# nigme1_Switch.net
KiCad netlist of a schematic drawn in Altium Designer
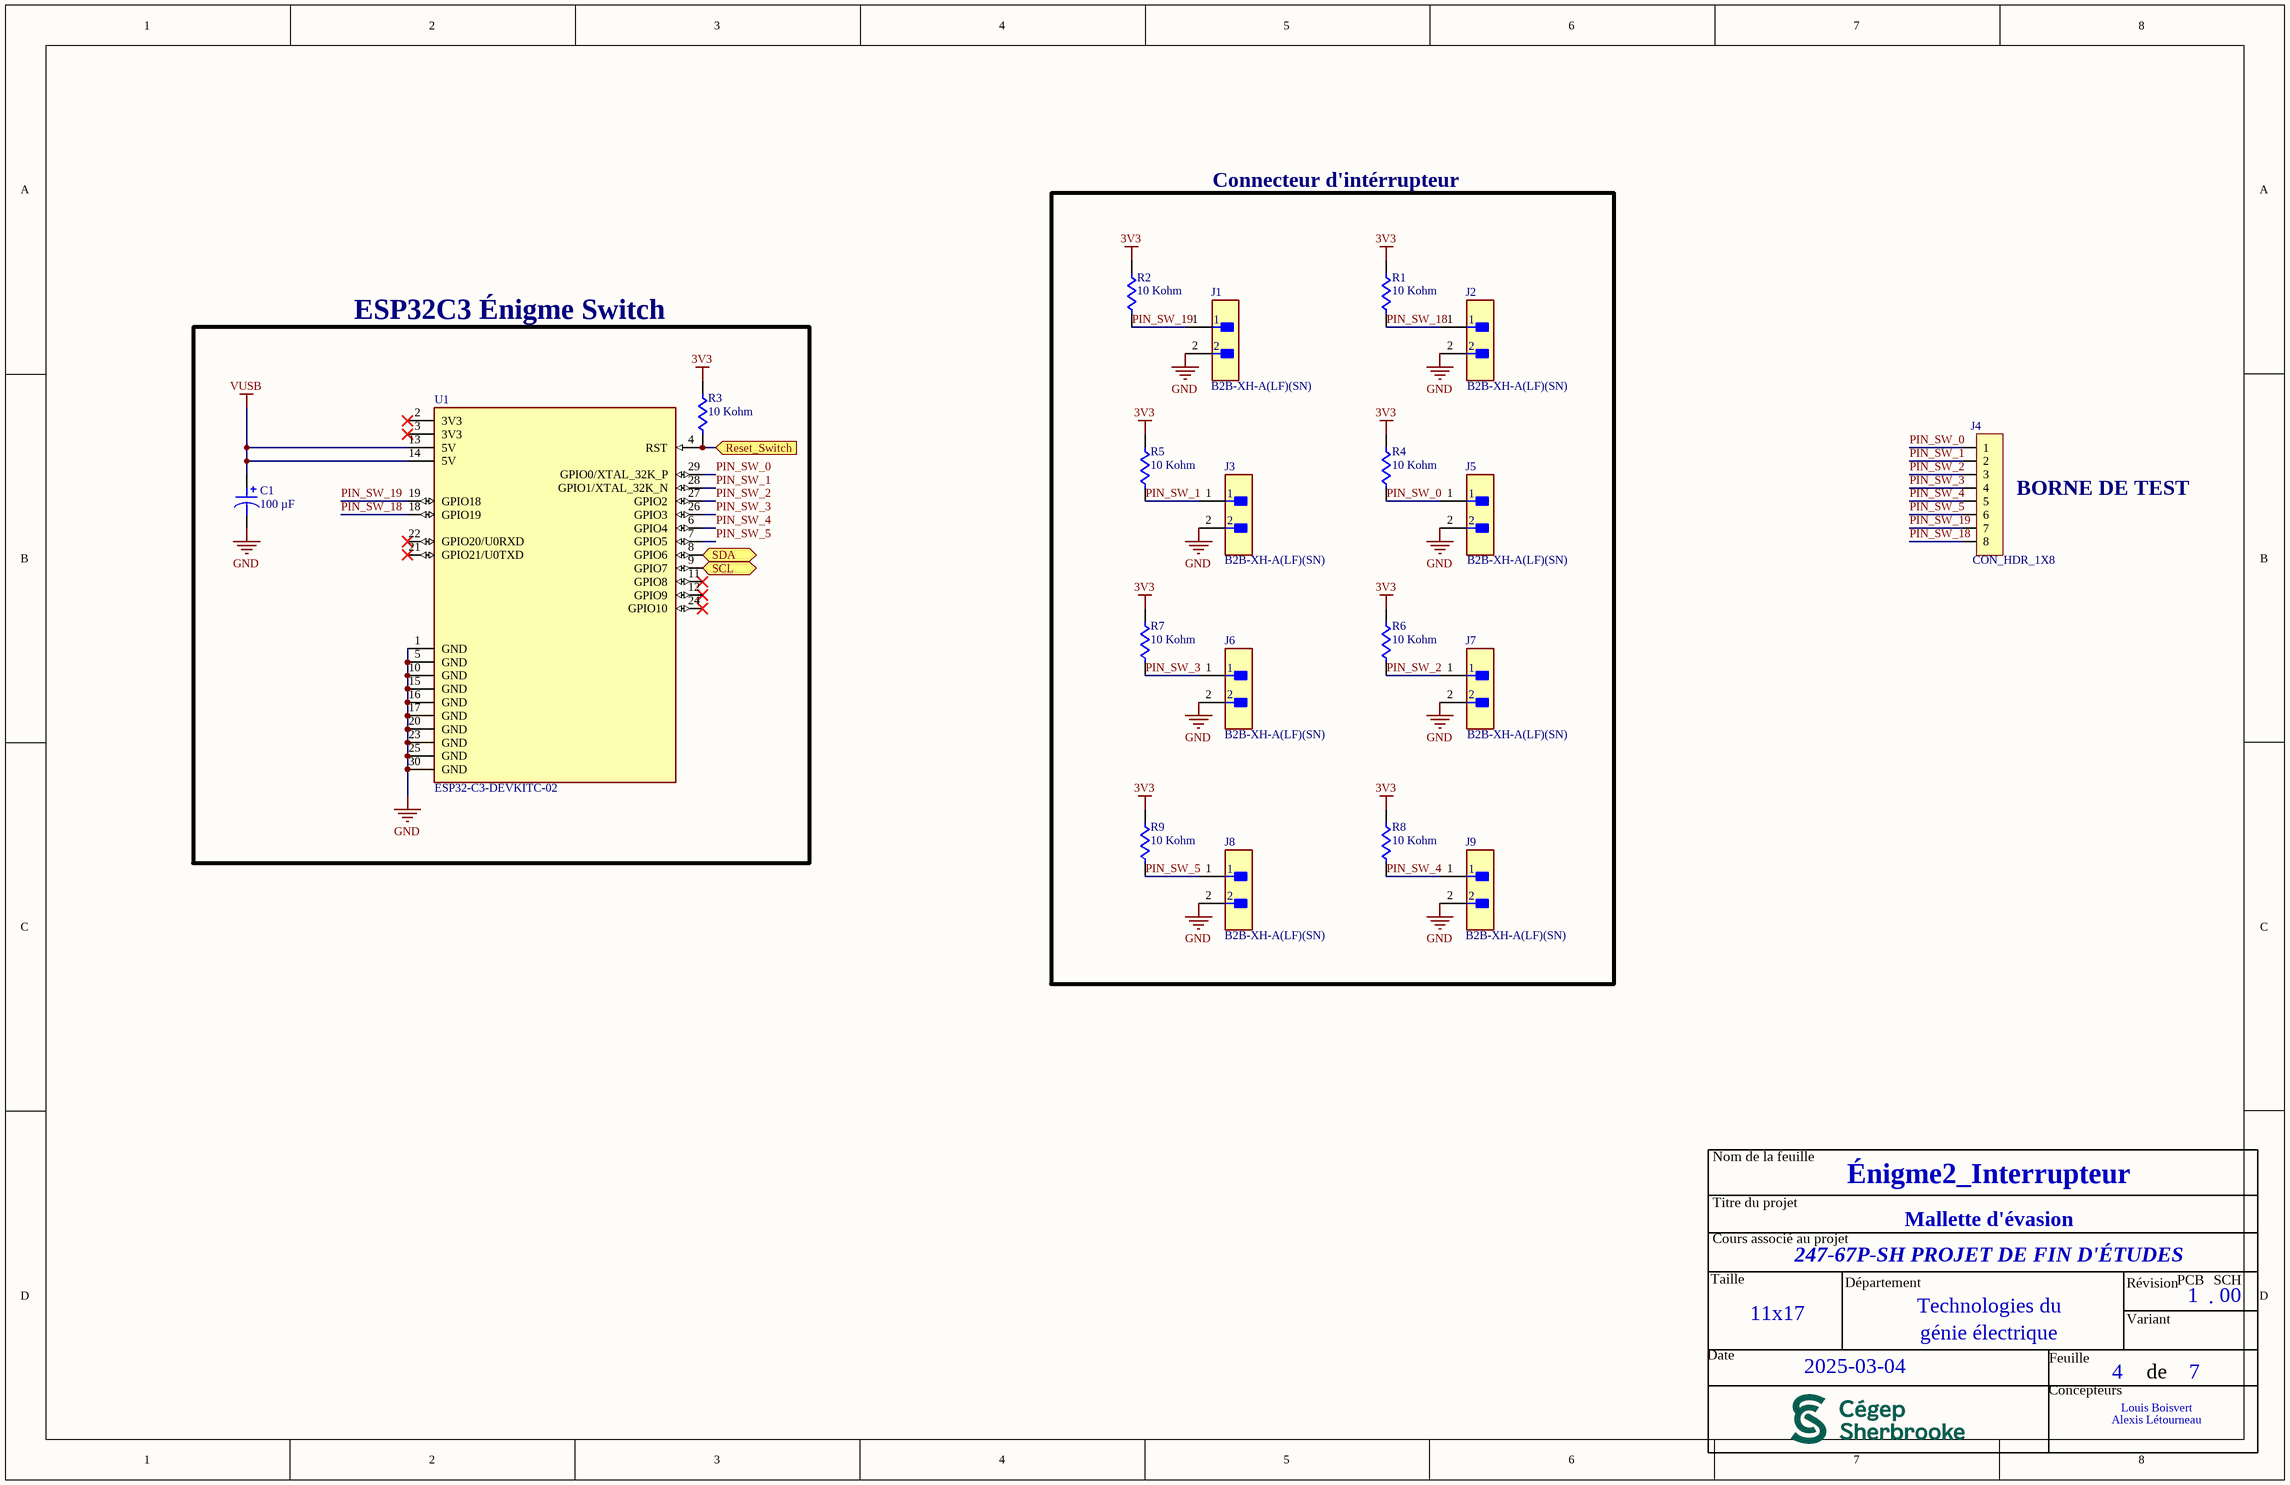
[diagram p0: Énigme1_Switch.SchDoc]

(export (version "E")
  (design (tool "Eeschema 10.0.6"))
  (components
    (comp (ref "C1")
      (value "100 µF")
      (footprint "CAP AL TH D8 L3.5 H12.5")
      (description "CAP ALUM 100UF 20% 50V RADIAL")
      (fields (field (name "PART NUMBER") "860020674015") (field (name "MANUFACTURER") "Würth Elektronik"))
      (libsource (lib "Celestial Altium Library - altium_library") (part "Polarised Capacitor"))
    )
    (comp (ref "J1")
      (value "B2B-XH-A(LF)(SN)")
      (footprint "FP-B2B-XH-A_LF_SN-MFG")
      (description "CONN HEADER VERT 2POS 2.5MM")
      (libsource (lib "Altium Content Vault") (part "3bc925449376181038e59eaffc5286c"))
    )
    (comp (ref "J2")
      (value "B2B-XH-A(LF)(SN)")
      (footprint "FP-B2B-XH-A_LF_SN-MFG")
      (description "CONN HEADER VERT 2POS 2.5MM")
      (libsource (lib "Altium Content Vault") (part "3bc925449376181038e59eaffc5286c"))
    )
    (comp (ref "J3")
      (value "B2B-XH-A(LF)(SN)")
      (footprint "FP-B2B-XH-A_LF_SN-MFG")
      (description "CONN HEADER VERT 2POS 2.5MM")
      (libsource (lib "Altium Content Vault") (part "3bc925449376181038e59eaffc5286c"))
    )
    (comp (ref "J4")
      (value "CON_HDR_1X8")
      (footprint "CON_HDR_1x8")
      (description "CON - Header 1X8 pins, 100Mils - TH-8")
      (fields (field (name "SOURCE") "CEGEP_SHERBROOKE_TGE_LIBRARY.SchLib"))
      (libsource (lib "Cegep de Sherbrooke") (part "CON_HDR_1X8"))
    )
    (comp (ref "J5")
      (value "B2B-XH-A(LF)(SN)")
      (footprint "FP-B2B-XH-A_LF_SN-MFG")
      (description "CONN HEADER VERT 2POS 2.5MM")
      (libsource (lib "Altium Content Vault") (part "3bc925449376181038e59eaffc5286c"))
    )
    (comp (ref "J6")
      (value "B2B-XH-A(LF)(SN)")
      (footprint "FP-B2B-XH-A_LF_SN-MFG")
      (description "CONN HEADER VERT 2POS 2.5MM")
      (libsource (lib "Altium Content Vault") (part "3bc925449376181038e59eaffc5286c"))
    )
    (comp (ref "J7")
      (value "B2B-XH-A(LF)(SN)")
      (footprint "FP-B2B-XH-A_LF_SN-MFG")
      (description "CONN HEADER VERT 2POS 2.5MM")
      (libsource (lib "Altium Content Vault") (part "3bc925449376181038e59eaffc5286c"))
    )
    (comp (ref "J8")
      (value "B2B-XH-A(LF)(SN)")
      (footprint "FP-B2B-XH-A_LF_SN-MFG")
      (description "CONN HEADER VERT 2POS 2.5MM")
      (libsource (lib "Altium Content Vault") (part "3bc925449376181038e59eaffc5286c"))
    )
    (comp (ref "J9")
      (value "B2B-XH-A(LF)(SN)")
      (footprint "FP-B2B-XH-A_LF_SN-MFG")
      (description "CONN HEADER VERT 2POS 2.5MM")
      (libsource (lib "Altium Content Vault") (part "3bc925449376181038e59eaffc5286c"))
    )
    (comp (ref "R1")
      (value "10 Kohm")
      (footprint "Res_Template")
      (description "Custom Semiconductor Resistor")
      (libsource (lib "Schlib1") (part "470 ohm"))
    )
    (comp (ref "R2")
      (value "10 Kohm")
      (footprint "Res_Template")
      (description "Custom Semiconductor Resistor")
      (libsource (lib "Schlib1") (part "470 ohm"))
    )
    (comp (ref "R3")
      (value "10 Kohm")
      (footprint "Res_Template")
      (description "Custom Semiconductor Resistor")
      (libsource (lib "Schlib1") (part "470 ohm"))
    )
    (comp (ref "R4")
      (value "10 Kohm")
      (footprint "Res_Template")
      (description "Custom Semiconductor Resistor")
      (libsource (lib "Schlib1") (part "470 ohm"))
    )
    (comp (ref "R5")
      (value "10 Kohm")
      (footprint "Res_Template")
      (description "Custom Semiconductor Resistor")
      (libsource (lib "Schlib1") (part "470 ohm"))
    )
    (comp (ref "R6")
      (value "10 Kohm")
      (footprint "Res_Template")
      (description "Custom Semiconductor Resistor")
      (libsource (lib "Schlib1") (part "470 ohm"))
    )
    (comp (ref "R7")
      (value "10 Kohm")
      (footprint "Res_Template")
      (description "Custom Semiconductor Resistor")
      (libsource (lib "Schlib1") (part "470 ohm"))
    )
    (comp (ref "R8")
      (value "10 Kohm")
      (footprint "Res_Template")
      (description "Custom Semiconductor Resistor")
      (libsource (lib "Schlib1") (part "470 ohm"))
    )
    (comp (ref "R9")
      (value "10 Kohm")
      (footprint "Res_Template")
      (description "Custom Semiconductor Resistor")
      (libsource (lib "Schlib1") (part "470 ohm"))
    )
    (comp (ref "U1")
      (value "ESP32-C3-DEVKITC-02")
      (footprint "XCVR_ESP32-C3-DEVKITC-02")
      (fields (field (name "MP") "ESP32-C3-DevKitC-02") (field (name "MF") "Espressif Systems"))
      (libsource (lib "ESP32-C3-DEVKITC-02") (part "ESP32-C3-DEVKITC-02"))
    )
  )
  (nets
    (net (code "1") (name "/PIN_SW_0") (class "Default")
      (node (ref "J4") (pin "1") (pinfunction "1_1") (pintype "passive"))
      (node (ref "J5") (pin "1") (pinfunction "1_1") (pintype "passive"))
      (node (ref "R4") (pin "1") (pinfunction "1_1") (pintype "passive"))
      (node (ref "U1") (pin "29") (pinfunction "GPIO0/XTAL_32K_P_29") (pintype "bidirectional"))
    )
    (net (code "2") (name "/PIN_SW_1") (class "Default")
      (node (ref "J3") (pin "1") (pinfunction "1_1") (pintype "passive"))
      (node (ref "J4") (pin "2") (pinfunction "2_2") (pintype "passive"))
      (node (ref "R5") (pin "1") (pinfunction "1_1") (pintype "passive"))
      (node (ref "U1") (pin "28") (pinfunction "GPIO1/XTAL_32K_N_28") (pintype "bidirectional"))
    )
    (net (code "3") (name "/PIN_SW_2") (class "Default")
      (node (ref "J4") (pin "3") (pinfunction "3_3") (pintype "passive"))
      (node (ref "J7") (pin "1") (pinfunction "1_1") (pintype "passive"))
      (node (ref "R6") (pin "1") (pinfunction "1_1") (pintype "passive"))
      (node (ref "U1") (pin "27") (pinfunction "GPIO2_27") (pintype "bidirectional"))
    )
    (net (code "4") (name "/PIN_SW_3") (class "Default")
      (node (ref "J4") (pin "4") (pinfunction "4_4") (pintype "passive"))
      (node (ref "J6") (pin "1") (pinfunction "1_1") (pintype "passive"))
      (node (ref "R7") (pin "1") (pinfunction "1_1") (pintype "passive"))
      (node (ref "U1") (pin "26") (pinfunction "GPIO3_26") (pintype "bidirectional"))
    )
    (net (code "5") (name "/PIN_SW_4") (class "Default")
      (node (ref "J4") (pin "5") (pinfunction "5_5") (pintype "passive"))
      (node (ref "J9") (pin "1") (pinfunction "1_1") (pintype "passive"))
      (node (ref "R8") (pin "1") (pinfunction "1_1") (pintype "passive"))
      (node (ref "U1") (pin "6") (pinfunction "GPIO4_6") (pintype "bidirectional"))
    )
    (net (code "6") (name "/PIN_SW_5") (class "Default")
      (node (ref "J4") (pin "6") (pinfunction "6_6") (pintype "passive"))
      (node (ref "J8") (pin "1") (pinfunction "1_1") (pintype "passive"))
      (node (ref "R9") (pin "1") (pinfunction "1_1") (pintype "passive"))
      (node (ref "U1") (pin "7") (pinfunction "GPIO5_7") (pintype "bidirectional"))
    )
    (net (code "7") (name "/PIN_SW_18") (class "Default")
      (node (ref "J2") (pin "1") (pinfunction "1_1") (pintype "passive"))
      (node (ref "J4") (pin "8") (pinfunction "8_8") (pintype "passive"))
      (node (ref "R1") (pin "1") (pinfunction "1_1") (pintype "passive"))
      (node (ref "U1") (pin "18") (pinfunction "GPIO19_18") (pintype "bidirectional"))
    )
    (net (code "8") (name "/PIN_SW_19") (class "Default")
      (node (ref "J1") (pin "1") (pinfunction "1_1") (pintype "passive"))
      (node (ref "J4") (pin "7") (pinfunction "7_7") (pintype "passive"))
      (node (ref "R2") (pin "1") (pinfunction "1_1") (pintype "passive"))
      (node (ref "U1") (pin "19") (pinfunction "GPIO18_19") (pintype "bidirectional"))
    )
    (net (code "9") (name "/Reset_Switch") (class "Default")
      (node (ref "R3") (pin "1") (pinfunction "1_1") (pintype "passive"))
      (node (ref "U1") (pin "4") (pinfunction "RST_4") (pintype "input"))
    )
    (net (code "10") (name "/SCL") (class "Default")
      (node (ref "U1") (pin "9") (pinfunction "GPIO7_9") (pintype "bidirectional"))
    )
    (net (code "11") (name "/SDA") (class "Default")
      (node (ref "U1") (pin "8") (pinfunction "GPIO6_8") (pintype "bidirectional"))
    )
    (net (code "12") (name "3V3") (class "Default")
      (node (ref "R1") (pin "2") (pinfunction "2_2") (pintype "passive"))
      (node (ref "R2") (pin "2") (pinfunction "2_2") (pintype "passive"))
      (node (ref "R3") (pin "2") (pinfunction "2_2") (pintype "passive"))
      (node (ref "R4") (pin "2") (pinfunction "2_2") (pintype "passive"))
      (node (ref "R5") (pin "2") (pinfunction "2_2") (pintype "passive"))
      (node (ref "R6") (pin "2") (pinfunction "2_2") (pintype "passive"))
      (node (ref "R7") (pin "2") (pinfunction "2_2") (pintype "passive"))
      (node (ref "R8") (pin "2") (pinfunction "2_2") (pintype "passive"))
      (node (ref "R9") (pin "2") (pinfunction "2_2") (pintype "passive"))
    )
    (net (code "13") (name "GND") (class "Default")
      (node (ref "C1") (pin "2") (pinfunction "2_2") (pintype "passive"))
      (node (ref "J1") (pin "2") (pinfunction "2_2") (pintype "passive"))
      (node (ref "J2") (pin "2") (pinfunction "2_2") (pintype "passive"))
      (node (ref "J3") (pin "2") (pinfunction "2_2") (pintype "passive"))
      (node (ref "J5") (pin "2") (pinfunction "2_2") (pintype "passive"))
      (node (ref "J6") (pin "2") (pinfunction "2_2") (pintype "passive"))
      (node (ref "J7") (pin "2") (pinfunction "2_2") (pintype "passive"))
      (node (ref "J8") (pin "2") (pinfunction "2_2") (pintype "passive"))
      (node (ref "J9") (pin "2") (pinfunction "2_2") (pintype "passive"))
      (node (ref "U1") (pin "1") (pinfunction "GND_1") (pintype "power_in"))
      (node (ref "U1") (pin "10") (pinfunction "GND_10") (pintype "power_in"))
      (node (ref "U1") (pin "15") (pinfunction "GND_15") (pintype "power_in"))
      (node (ref "U1") (pin "16") (pinfunction "GND_16") (pintype "power_in"))
      (node (ref "U1") (pin "17") (pinfunction "GND_17") (pintype "power_in"))
      (node (ref "U1") (pin "20") (pinfunction "GND_20") (pintype "power_in"))
      (node (ref "U1") (pin "23") (pinfunction "GND_23") (pintype "power_in"))
      (node (ref "U1") (pin "25") (pinfunction "GND_25") (pintype "power_in"))
      (node (ref "U1") (pin "30") (pinfunction "GND_30") (pintype "power_in"))
      (node (ref "U1") (pin "5") (pinfunction "GND_5") (pintype "power_in"))
    )
    (net (code "14") (name "VUSB") (class "Default")
      (node (ref "C1") (pin "1") (pinfunction "1_1") (pintype "passive"))
      (node (ref "U1") (pin "13") (pinfunction "5V_13") (pintype "power_in"))
      (node (ref "U1") (pin "14") (pinfunction "5V_14") (pintype "power_in"))
    )
    (net (code "15") (name "unconnected-(U1-3V3-Pad2)") (class "Default")
      (node (ref "U1") (pin "2") (pinfunction "3V3_2") (pintype "power_in+no_connect"))
    )
    (net (code "16") (name "unconnected-(U1-3V3-Pad3)") (class "Default")
      (node (ref "U1") (pin "3") (pinfunction "3V3_3") (pintype "power_in+no_connect"))
    )
    (net (code "17") (name "unconnected-(U1-GPIO8-Pad11)") (class "Default")
      (node (ref "U1") (pin "11") (pinfunction "GPIO8_11") (pintype "bidirectional+no_connect"))
    )
    (net (code "18") (name "unconnected-(U1-GPIO9-Pad12)") (class "Default")
      (node (ref "U1") (pin "12") (pinfunction "GPIO9_12") (pintype "bidirectional+no_connect"))
    )
    (net (code "19") (name "unconnected-(U1-GPIO10-Pad24)") (class "Default")
      (node (ref "U1") (pin "24") (pinfunction "GPIO10_24") (pintype "bidirectional+no_connect"))
    )
    (net (code "20") (name "unconnected-(U1-GPIO20{slash}U0RXD-Pad22)") (class "Default")
      (node (ref "U1") (pin "22") (pinfunction "GPIO20/U0RXD_22") (pintype "bidirectional+no_connect"))
    )
    (net (code "21") (name "unconnected-(U1-GPIO21{slash}U0TXD-Pad21)") (class "Default")
      (node (ref "U1") (pin "21") (pinfunction "GPIO21/U0TXD_21") (pintype "bidirectional+no_connect"))
    )
  )
)
